# ESP32-RFID_IoT_V2.net
KiCad netlist of a schematic drawn in EAGLE
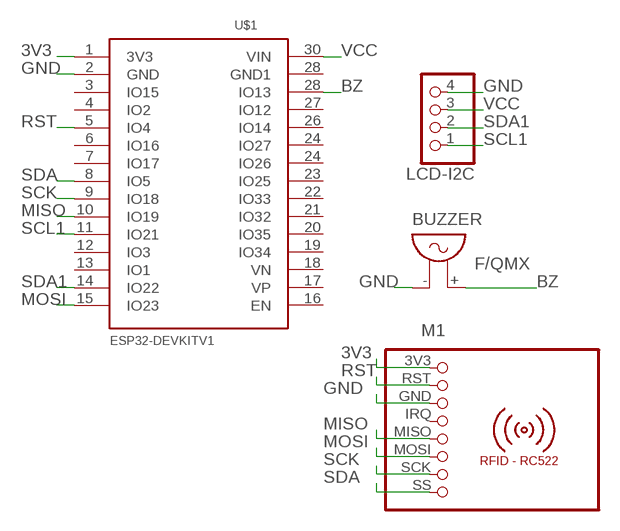
[diagram p0: schematic, sheet 1]

(export (version "E")
  (design (tool "Eeschema 10.0.6"))
  (components
    (comp (ref "BUZZER")
      (value "F/QMX")
      (footprint "eagle-import:F_QMX")
      (libsource (lib "eagle-import") (part "F/QMX"))
    )
    (comp (ref "LCD-I2C")
      (value "PINHD-1X4")
      (footprint "eagle-import:1X04")
      (libsource (lib "eagle-import") (part "PINHD-1X4"))
    )
    (comp (ref "M1")
      (value "RFID-RC522")
      (footprint "eagle-import:RFID-RC522")
      (libsource (lib "eagle-import") (part "RFID-RC522"))
    )
    (comp (ref "U$1")
      (value "ESP32DEVKITV1")
      (footprint "eagle-import:ESP32-DEVKITV1")
      (libsource (lib "eagle-import") (part "ESP32DEVKITV1"))
    )
  )
  (nets
    (net (code "1") (name "/3V3") (class "Default")
      (node (ref "M1") (pin "3V3") (pinfunction "1_3V3") (pintype "passive"))
      (node (ref "U$1") (pin "1") (pinfunction "3V3_1") (pintype "bidirectional"))
    )
    (net (code "2") (name "/BZ") (class "Default")
      (node (ref "BUZZER") (pin "+") (pinfunction "2_+") (pintype "passive"))
      (node (ref "U$1") (pin "28") (pinfunction "IO13_28") (pintype "bidirectional"))
    )
    (net (code "3") (name "/GND") (class "Default")
      (node (ref "BUZZER") (pin "-") (pinfunction "1_-") (pintype "passive"))
      (node (ref "LCD-I2C") (pin "4") (pinfunction "4_4") (pintype "passive"))
      (node (ref "M1") (pin "GND") (pinfunction "3_GND") (pintype "passive"))
      (node (ref "U$1") (pin "2") (pinfunction "GND_2") (pintype "bidirectional"))
    )
    (net (code "4") (name "/MISO") (class "Default")
      (node (ref "M1") (pin "MISO") (pinfunction "5_MISO") (pintype "passive"))
      (node (ref "U$1") (pin "10") (pinfunction "IO19_10") (pintype "bidirectional"))
    )
    (net (code "5") (name "/MOSI") (class "Default")
      (node (ref "M1") (pin "MOSI") (pinfunction "6_MOSI") (pintype "passive"))
      (node (ref "U$1") (pin "15") (pinfunction "IO23_15") (pintype "bidirectional"))
    )
    (net (code "6") (name "/RST") (class "Default")
      (node (ref "M1") (pin "RST") (pinfunction "2_RST") (pintype "passive"))
      (node (ref "U$1") (pin "5") (pinfunction "IO4_5") (pintype "bidirectional"))
    )
    (net (code "7") (name "/SCK") (class "Default")
      (node (ref "M1") (pin "SCK") (pinfunction "7_SCK") (pintype "passive"))
      (node (ref "U$1") (pin "9") (pinfunction "IO18_9") (pintype "bidirectional"))
    )
    (net (code "8") (name "/SCL1") (class "Default")
      (node (ref "LCD-I2C") (pin "1") (pinfunction "1_1") (pintype "passive"))
      (node (ref "U$1") (pin "11") (pinfunction "IO21_11") (pintype "bidirectional"))
    )
    (net (code "9") (name "/SDA") (class "Default")
      (node (ref "M1") (pin "SS") (pinfunction "8_SS") (pintype "passive"))
      (node (ref "U$1") (pin "8") (pinfunction "IO5_8") (pintype "bidirectional"))
    )
    (net (code "10") (name "/SDA1") (class "Default")
      (node (ref "LCD-I2C") (pin "2") (pinfunction "2_2") (pintype "passive"))
      (node (ref "U$1") (pin "14") (pinfunction "IO22_14") (pintype "bidirectional"))
    )
    (net (code "11") (name "/VCC") (class "Default")
      (node (ref "LCD-I2C") (pin "3") (pinfunction "3_3") (pintype "passive"))
      (node (ref "U$1") (pin "30") (pinfunction "VIN_30") (pintype "bidirectional"))
    )
    (net (code "12") (name "unconnected-(M1-4-PadIRQ)") (class "Default")
      (node (ref "M1") (pin "IRQ") (pinfunction "4_IRQ") (pintype "passive"))
    )
    (net (code "13") (name "unconnected-(U$1-EN-Pad16)") (class "Default")
      (node (ref "U$1") (pin "16") (pinfunction "EN_16") (pintype "bidirectional"))
    )
    (net (code "14") (name "unconnected-(U$1-GND1-Pad28)") (class "Default")
      (node (ref "U$1") (pin "28") (pinfunction "GND1_28") (pintype "bidirectional"))
    )
    (net (code "15") (name "unconnected-(U$1-IO1-Pad13)") (class "Default")
      (node (ref "U$1") (pin "13") (pinfunction "IO1_13") (pintype "bidirectional"))
    )
    (net (code "16") (name "unconnected-(U$1-IO2-Pad4)") (class "Default")
      (node (ref "U$1") (pin "4") (pinfunction "IO2_4") (pintype "bidirectional"))
    )
    (net (code "17") (name "unconnected-(U$1-IO3-Pad12)") (class "Default")
      (node (ref "U$1") (pin "12") (pinfunction "IO3_12") (pintype "bidirectional"))
    )
    (net (code "18") (name "unconnected-(U$1-IO12-Pad27)") (class "Default")
      (node (ref "U$1") (pin "27") (pinfunction "IO12_27") (pintype "bidirectional"))
    )
    (net (code "19") (name "unconnected-(U$1-IO14-Pad26)") (class "Default")
      (node (ref "U$1") (pin "26") (pinfunction "IO14_26") (pintype "bidirectional"))
    )
    (net (code "20") (name "unconnected-(U$1-IO15-Pad3)") (class "Default")
      (node (ref "U$1") (pin "3") (pinfunction "IO15_3") (pintype "bidirectional"))
    )
    (net (code "21") (name "unconnected-(U$1-IO16-Pad6)") (class "Default")
      (node (ref "U$1") (pin "6") (pinfunction "IO16_6") (pintype "bidirectional"))
    )
    (net (code "22") (name "unconnected-(U$1-IO17-Pad7)") (class "Default")
      (node (ref "U$1") (pin "7") (pinfunction "IO17_7") (pintype "bidirectional"))
    )
    (net (code "23") (name "unconnected-(U$1-IO25-Pad23)") (class "Default")
      (node (ref "U$1") (pin "23") (pinfunction "IO25_23") (pintype "bidirectional"))
    )
    (net (code "24") (name "unconnected-(U$1-IO26-Pad24)") (class "Default")
      (node (ref "U$1") (pin "24") (pinfunction "IO26_24") (pintype "bidirectional"))
    )
    (net (code "25") (name "unconnected-(U$1-IO27-Pad24)") (class "Default")
      (node (ref "U$1") (pin "24") (pinfunction "IO27_24") (pintype "bidirectional"))
    )
    (net (code "26") (name "unconnected-(U$1-IO32-Pad21)") (class "Default")
      (node (ref "U$1") (pin "21") (pinfunction "IO32_21") (pintype "bidirectional"))
    )
    (net (code "27") (name "unconnected-(U$1-IO33-Pad22)") (class "Default")
      (node (ref "U$1") (pin "22") (pinfunction "IO33_22") (pintype "bidirectional"))
    )
    (net (code "28") (name "unconnected-(U$1-IO34-Pad19)") (class "Default")
      (node (ref "U$1") (pin "19") (pinfunction "IO34_19") (pintype "bidirectional"))
    )
    (net (code "29") (name "unconnected-(U$1-IO35-Pad20)") (class "Default")
      (node (ref "U$1") (pin "20") (pinfunction "IO35_20") (pintype "bidirectional"))
    )
    (net (code "30") (name "unconnected-(U$1-VN-Pad18)") (class "Default")
      (node (ref "U$1") (pin "18") (pinfunction "VN_18") (pintype "bidirectional"))
    )
    (net (code "31") (name "unconnected-(U$1-VP-Pad17)") (class "Default")
      (node (ref "U$1") (pin "17") (pinfunction "VP_17") (pintype "bidirectional"))
    )
  )
)
